# 150306_AriloRX_REV2_0_0.net
KiCad netlist of a schematic drawn in EAGLE
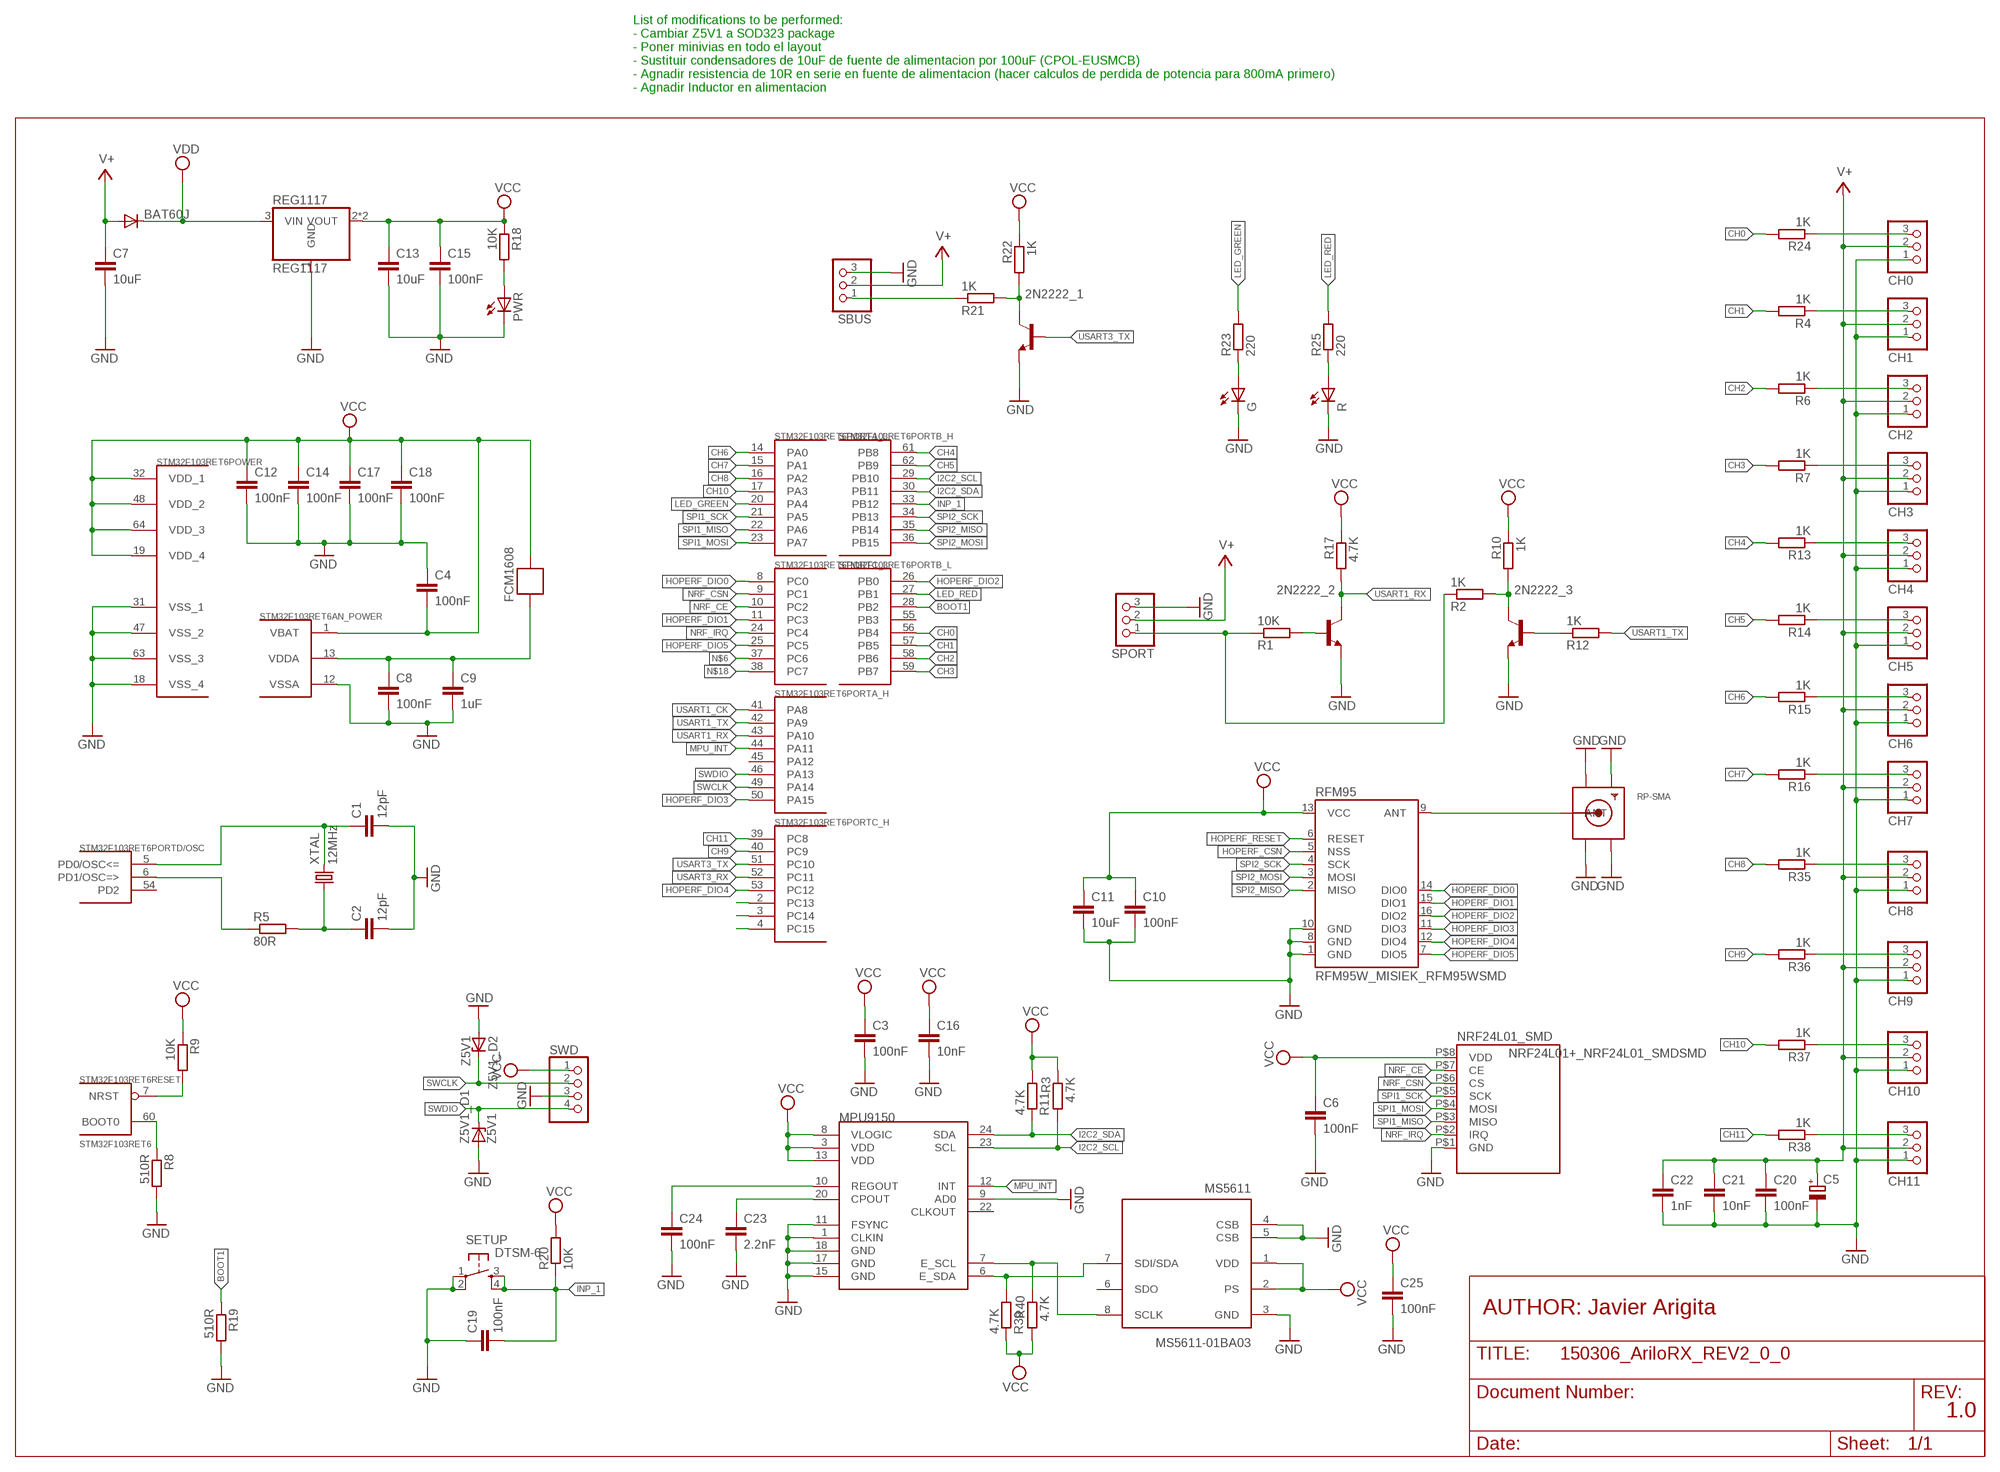
[diagram p0: schematic, sheet 1]

(export (version "E")
  (design (tool "Eeschema 10.0.6"))
  (components
    (comp (ref "2N2222_1")
      (value "MMBT2222ALT1-NPN-SOT23-BEC")
      (footprint "eagle-import:SOT23-BEC")
      (libsource (lib "eagle-import") (part "-NPN-SOT23-BECMMBT2222ALT1"))
    )
    (comp (ref "2N2222_2")
      (value "MMBT2222ALT1-NPN-SOT23-BEC")
      (footprint "eagle-import:SOT23-BEC")
      (libsource (lib "eagle-import") (part "-NPN-SOT23-BECMMBT2222ALT1"))
    )
    (comp (ref "2N2222_3")
      (value "MMBT2222ALT1-NPN-SOT23-BEC")
      (footprint "eagle-import:SOT23-BEC")
      (libsource (lib "eagle-import") (part "-NPN-SOT23-BECMMBT2222ALT1"))
    )
    (comp (ref "BAT60J")
      (value "DIODE-SOD323-R")
      (footprint "eagle-import:SOD323-R")
      (libsource (lib "eagle-import") (part "DIODE-SOD323-R"))
    )
    (comp (ref "C1")
      (value "12pF")
      (footprint "eagle-import:RESISTOR_C0603")
      (libsource (lib "eagle-import") (part "RESISTOR_C-EUC0603"))
    )
    (comp (ref "C2")
      (value "12pF")
      (footprint "eagle-import:RESISTOR_C0603")
      (libsource (lib "eagle-import") (part "RESISTOR_C-EUC0603"))
    )
    (comp (ref "C3")
      (value "100nF")
      (footprint "eagle-import:RESISTOR_C0603")
      (libsource (lib "eagle-import") (part "RESISTOR_C-EUC0603"))
    )
    (comp (ref "C4")
      (value "100nF")
      (footprint "eagle-import:RESISTOR_C0603")
      (libsource (lib "eagle-import") (part "RESISTOR_C-EUC0603"))
    )
    (comp (ref "C5")
      (value "CPOL-EUSMCB")
      (footprint "eagle-import:SMC_B")
      (libsource (lib "eagle-import") (part "CPOL-EUSMCB"))
    )
    (comp (ref "C6")
      (value "100nF")
      (footprint "eagle-import:RESISTOR_C0603")
      (libsource (lib "eagle-import") (part "RESISTOR_C-EUC0603"))
    )
    (comp (ref "C7")
      (value "10uF")
      (footprint "eagle-import:RESISTOR_C3216")
      (libsource (lib "eagle-import") (part "RESISTOR_C-EUC3216"))
    )
    (comp (ref "C8")
      (value "100nF")
      (footprint "eagle-import:RESISTOR_C0603")
      (libsource (lib "eagle-import") (part "RESISTOR_C-EUC0603"))
    )
    (comp (ref "C9")
      (value "1uF")
      (footprint "eagle-import:RESISTOR_C0603")
      (libsource (lib "eagle-import") (part "RESISTOR_C-EUC0603"))
    )
    (comp (ref "C10")
      (value "100nF")
      (footprint "eagle-import:RESISTOR_C0603")
      (libsource (lib "eagle-import") (part "RESISTOR_C-EUC0603"))
    )
    (comp (ref "C11")
      (value "10uF")
      (footprint "eagle-import:RESISTOR_C3216")
      (libsource (lib "eagle-import") (part "RESISTOR_C-EUC3216"))
    )
    (comp (ref "C12")
      (value "100nF")
      (footprint "eagle-import:RESISTOR_C0603")
      (libsource (lib "eagle-import") (part "RESISTOR_C-EUC0603"))
    )
    (comp (ref "C13")
      (value "10uF")
      (footprint "eagle-import:RESISTOR_C3216")
      (libsource (lib "eagle-import") (part "RESISTOR_C-EUC3216"))
    )
    (comp (ref "C14")
      (value "100nF")
      (footprint "eagle-import:RESISTOR_C0603")
      (libsource (lib "eagle-import") (part "RESISTOR_C-EUC0603"))
    )
    (comp (ref "C15")
      (value "100nF")
      (footprint "eagle-import:RESISTOR_C0603")
      (libsource (lib "eagle-import") (part "RESISTOR_C-EUC0603"))
    )
    (comp (ref "C16")
      (value "10nF")
      (footprint "eagle-import:RESISTOR_C0603")
      (libsource (lib "eagle-import") (part "RESISTOR_C-EUC0603"))
    )
    (comp (ref "C17")
      (value "100nF")
      (footprint "eagle-import:RESISTOR_C0603")
      (libsource (lib "eagle-import") (part "RESISTOR_C-EUC0603"))
    )
    (comp (ref "C18")
      (value "100nF")
      (footprint "eagle-import:RESISTOR_C0603")
      (libsource (lib "eagle-import") (part "RESISTOR_C-EUC0603"))
    )
    (comp (ref "C19")
      (value "100nF")
      (footprint "eagle-import:RESISTOR_C0603")
      (libsource (lib "eagle-import") (part "RESISTOR_C-EUC0603"))
    )
    (comp (ref "C20")
      (value "100nF")
      (footprint "eagle-import:RESISTOR_C0603")
      (libsource (lib "eagle-import") (part "RESISTOR_C-EUC0603"))
    )
    (comp (ref "C21")
      (value "10nF")
      (footprint "eagle-import:RESISTOR_C0603")
      (libsource (lib "eagle-import") (part "RESISTOR_C-EUC0603"))
    )
    (comp (ref "C22")
      (value "1nF")
      (footprint "eagle-import:RESISTOR_C0603")
      (libsource (lib "eagle-import") (part "RESISTOR_C-EUC0603"))
    )
    (comp (ref "C23")
      (value "2.2nF")
      (footprint "eagle-import:RESISTOR_C0603")
      (libsource (lib "eagle-import") (part "RESISTOR_C-EUC0603"))
    )
    (comp (ref "C24")
      (value "100nF")
      (footprint "eagle-import:RESISTOR_C0603")
      (libsource (lib "eagle-import") (part "RESISTOR_C-EUC0603"))
    )
    (comp (ref "C25")
      (value "100nF")
      (footprint "eagle-import:RESISTOR_C0603")
      (libsource (lib "eagle-import") (part "RESISTOR_C-EUC0603"))
    )
    (comp (ref "CH0")
      (value "PINHD-1X3")
      (footprint "eagle-import:1X03")
      (libsource (lib "eagle-import") (part "PINHD-1X3"))
    )
    (comp (ref "CH1")
      (value "PINHD-1X3")
      (footprint "eagle-import:1X03")
      (libsource (lib "eagle-import") (part "PINHD-1X3"))
    )
    (comp (ref "CH2")
      (value "PINHD-1X3")
      (footprint "eagle-import:1X03")
      (libsource (lib "eagle-import") (part "PINHD-1X3"))
    )
    (comp (ref "CH3")
      (value "PINHD-1X3")
      (footprint "eagle-import:1X03")
      (libsource (lib "eagle-import") (part "PINHD-1X3"))
    )
    (comp (ref "CH4")
      (value "PINHD-1X3")
      (footprint "eagle-import:1X03")
      (libsource (lib "eagle-import") (part "PINHD-1X3"))
    )
    (comp (ref "CH5")
      (value "PINHD-1X3")
      (footprint "eagle-import:1X03")
      (libsource (lib "eagle-import") (part "PINHD-1X3"))
    )
    (comp (ref "CH6")
      (value "PINHD-1X3")
      (footprint "eagle-import:1X03")
      (libsource (lib "eagle-import") (part "PINHD-1X3"))
    )
    (comp (ref "CH7")
      (value "PINHD-1X3")
      (footprint "eagle-import:1X03")
      (libsource (lib "eagle-import") (part "PINHD-1X3"))
    )
    (comp (ref "CH8")
      (value "PINHD-1X3")
      (footprint "eagle-import:1X03")
      (libsource (lib "eagle-import") (part "PINHD-1X3"))
    )
    (comp (ref "CH9")
      (value "PINHD-1X3")
      (footprint "eagle-import:1X03")
      (libsource (lib "eagle-import") (part "PINHD-1X3"))
    )
    (comp (ref "CH10")
      (value "PINHD-1X3")
      (footprint "eagle-import:1X03")
      (libsource (lib "eagle-import") (part "PINHD-1X3"))
    )
    (comp (ref "CH11")
      (value "PINHD-1X3")
      (footprint "eagle-import:1X03")
      (libsource (lib "eagle-import") (part "PINHD-1X3"))
    )
    (comp (ref "FCM1608")
      (value "FERRITE-BEAD")
      (footprint "eagle-import:R0603")
      (libsource (lib "eagle-import") (part "FERRITE-BEAD"))
    )
    (comp (ref "G")
      (value "LEDCHIP-LED0603")
      (footprint "eagle-import:CHIP-LED0603")
      (libsource (lib "eagle-import") (part "LEDCHIP-LED0603"))
    )
    (comp (ref "MPU9150")
      (value "MPU-9150QFN-24-NP")
      (footprint "eagle-import:QFN-24-NP")
      (libsource (lib "eagle-import") (part "MPU-9150QFN-24-NP"))
    )
    (comp (ref "MS5611")
      (value "MS5611-01BA03")
      (footprint "eagle-import:SON125P300X500X100-8N")
      (libsource (lib "eagle-import") (part "MS5611-01BA03"))
    )
    (comp (ref "NRF24L01_SMD")
      (value "NRF24L01+_NRF24L01_SMDSMD")
      (footprint "eagle-import:NRF24L01+_NRF24L01_SMD")
      (libsource (lib "eagle-import") (part "NRF24L01+_NRF24L01_SMDSMD"))
    )
    (comp (ref "PWR")
      (value "LED_LEDCHIP-LED0603")
      (footprint "eagle-import:LED_CHIP-LED0603")
      (libsource (lib "eagle-import") (part "LED_LEDCHIP-LED0603"))
    )
    (comp (ref "R")
      (value "LEDCHIP-LED0603")
      (footprint "eagle-import:CHIP-LED0603")
      (libsource (lib "eagle-import") (part "LEDCHIP-LED0603"))
    )
    (comp (ref "R1")
      (value "10K")
      (footprint "eagle-import:RCL_R0603")
      (libsource (lib "eagle-import") (part "RCL_R-EU_R0603"))
    )
    (comp (ref "R2")
      (value "1K")
      (footprint "eagle-import:RCL_R0603")
      (libsource (lib "eagle-import") (part "RCL_R-EU_R0603"))
    )
    (comp (ref "R3")
      (value "4.7K")
      (footprint "eagle-import:RCL_R0603")
      (libsource (lib "eagle-import") (part "RCL_R-EU_R0603"))
    )
    (comp (ref "R4")
      (value "1K")
      (footprint "eagle-import:RCL_R0603")
      (libsource (lib "eagle-import") (part "RCL_R-EU_R0603"))
    )
    (comp (ref "R5")
      (value "80R")
      (footprint "eagle-import:RCL_R0603")
      (libsource (lib "eagle-import") (part "RCL_R-EU_R0603"))
    )
    (comp (ref "R6")
      (value "1K")
      (footprint "eagle-import:RCL_R0603")
      (libsource (lib "eagle-import") (part "RCL_R-EU_R0603"))
    )
    (comp (ref "R7")
      (value "1K")
      (footprint "eagle-import:RCL_R0603")
      (libsource (lib "eagle-import") (part "RCL_R-EU_R0603"))
    )
    (comp (ref "R8")
      (value "510R")
      (footprint "eagle-import:RCL_R0603")
      (libsource (lib "eagle-import") (part "RCL_R-EU_R0603"))
    )
    (comp (ref "R9")
      (value "10K")
      (footprint "eagle-import:RCL_R0603")
      (libsource (lib "eagle-import") (part "RCL_R-EU_R0603"))
    )
    (comp (ref "R10")
      (value "1K")
      (footprint "eagle-import:RCL_R0603")
      (libsource (lib "eagle-import") (part "RCL_R-EU_R0603"))
    )
    (comp (ref "R11")
      (value "4.7K")
      (footprint "eagle-import:RCL_R0603")
      (libsource (lib "eagle-import") (part "RCL_R-EU_R0603"))
    )
    (comp (ref "R12")
      (value "1K")
      (footprint "eagle-import:RCL_R0603")
      (libsource (lib "eagle-import") (part "RCL_R-EU_R0603"))
    )
    (comp (ref "R13")
      (value "1K")
      (footprint "eagle-import:RCL_R0603")
      (libsource (lib "eagle-import") (part "RCL_R-EU_R0603"))
    )
    (comp (ref "R14")
      (value "1K")
      (footprint "eagle-import:RCL_R0603")
      (libsource (lib "eagle-import") (part "RCL_R-EU_R0603"))
    )
    (comp (ref "R15")
      (value "1K")
      (footprint "eagle-import:RCL_R0603")
      (libsource (lib "eagle-import") (part "RCL_R-EU_R0603"))
    )
    (comp (ref "R16")
      (value "1K")
      (footprint "eagle-import:RCL_R0603")
      (libsource (lib "eagle-import") (part "RCL_R-EU_R0603"))
    )
    (comp (ref "R17")
      (value "4.7K")
      (footprint "eagle-import:RCL_R0603")
      (libsource (lib "eagle-import") (part "RCL_R-EU_R0603"))
    )
    (comp (ref "R18")
      (value "10K")
      (footprint "eagle-import:RCL_R0603")
      (libsource (lib "eagle-import") (part "RCL_R-EU_R0603"))
    )
    (comp (ref "R19")
      (value "510R")
      (footprint "eagle-import:RCL_R0603")
      (libsource (lib "eagle-import") (part "RCL_R-EU_R0603"))
    )
    (comp (ref "R20")
      (value "10K")
      (footprint "eagle-import:RCL_R0603")
      (libsource (lib "eagle-import") (part "RCL_R-EU_R0603"))
    )
    (comp (ref "R21")
      (value "1K")
      (footprint "eagle-import:RCL_R0603")
      (libsource (lib "eagle-import") (part "RCL_R-EU_R0603"))
    )
    (comp (ref "R22")
      (value "1K")
      (footprint "eagle-import:RCL_R0603")
      (libsource (lib "eagle-import") (part "RCL_R-EU_R0603"))
    )
    (comp (ref "R23")
      (value "220")
      (footprint "eagle-import:RCL_R0603")
      (libsource (lib "eagle-import") (part "RCL_R-EU_R0603"))
    )
    (comp (ref "R24")
      (value "1K")
      (footprint "eagle-import:RCL_R0603")
      (libsource (lib "eagle-import") (part "RCL_R-EU_R0603"))
    )
    (comp (ref "R25")
      (value "220")
      (footprint "eagle-import:RCL_R0603")
      (libsource (lib "eagle-import") (part "RCL_R-EU_R0603"))
    )
    (comp (ref "R35")
      (value "1K")
      (footprint "eagle-import:RCL_R0603")
      (libsource (lib "eagle-import") (part "RCL_R-EU_R0603"))
    )
    (comp (ref "R36")
      (value "1K")
      (footprint "eagle-import:RCL_R0603")
      (libsource (lib "eagle-import") (part "RCL_R-EU_R0603"))
    )
    (comp (ref "R37")
      (value "1K")
      (footprint "eagle-import:RCL_R0603")
      (libsource (lib "eagle-import") (part "RCL_R-EU_R0603"))
    )
    (comp (ref "R38")
      (value "1K")
      (footprint "eagle-import:RCL_R0603")
      (libsource (lib "eagle-import") (part "RCL_R-EU_R0603"))
    )
    (comp (ref "R39")
      (value "4.7K")
      (footprint "eagle-import:RCL_R0603")
      (libsource (lib "eagle-import") (part "RCL_R-EU_R0603"))
    )
    (comp (ref "R40")
      (value "4.7K")
      (footprint "eagle-import:RCL_R0603")
      (libsource (lib "eagle-import") (part "RCL_R-EU_R0603"))
    )
    (comp (ref "REG1117")
      (value "REG1117")
      (footprint "eagle-import:SOT223")
      (libsource (lib "eagle-import") (part "REG1117"))
    )
    (comp (ref "RFM95")
      (value "RFM95W_MISIEK_RFM95WSMD")
      (footprint "eagle-import:RFM95W_MISIEK_RFM95W_SMD")
      (libsource (lib "eagle-import") (part "RFM95W_MISIEK_RFM95WSMD"))
    )
    (comp (ref "RP-SMA")
      (value "SMACONNECTOR_EDGE")
      (footprint "eagle-import:SMA_EDGELAUNCH")
      (libsource (lib "eagle-import") (part "SMACONNECTOR_EDGE"))
    )
    (comp (ref "SBUS")
      (value "PINHD-1X3")
      (footprint "eagle-import:1X03")
      (libsource (lib "eagle-import") (part "PINHD-1X3"))
    )
    (comp (ref "SETUP")
      (value "DTSM-6")
      (footprint "eagle-import:DTSM-6")
      (libsource (lib "eagle-import") (part "DTSM-6"))
    )
    (comp (ref "SPORT")
      (value "PINHD-1X3")
      (footprint "eagle-import:1X03")
      (libsource (lib "eagle-import") (part "PINHD-1X3"))
    )
    (comp (ref "STM32F103RET6")
      (value "STM32F103RET6")
      (footprint "eagle-import:TQFP64")
      (libsource (lib "eagle-import") (part "STM32F10XRXT6"))
    )
    (comp (ref "SWD")
      (value "PINHD-1X4")
      (footprint "eagle-import:1X04")
      (libsource (lib "eagle-import") (part "PINHD-1X4"))
    )
    (comp (ref "XTAL")
      (value "12MHz")
      (footprint "eagle-import:CRYSTAL-SMD-5X3")
      (libsource (lib "eagle-import") (part "CRYSTAL5X3"))
    )
    (comp (ref "Z5V1_D1")
      (value "Z5V1")
      (footprint "eagle-import:SOD80C")
      (libsource (lib "eagle-import") (part "ZENER-DIODESOD80C"))
    )
    (comp (ref "Z5V1_D2")
      (value "Z5V1")
      (footprint "eagle-import:SOD80C")
      (libsource (lib "eagle-import") (part "ZENER-DIODESOD80C"))
    )
  )
  (nets
    (net (code "1") (name "BOOT1") (class "Default")
      (node (ref "R19") (pin "1") (pinfunction "1_1") (pintype "passive"))
      (node (ref "STM32F103RET6") (pin "28") (pinfunction "PB2_28") (pintype "bidirectional"))
    )
    (net (code "2") (name "CH0") (class "Default")
      (node (ref "R24") (pin "2") (pinfunction "2_2") (pintype "passive"))
      (node (ref "STM32F103RET6") (pin "56") (pinfunction "PB4_56") (pintype "bidirectional"))
    )
    (net (code "3") (name "CH1") (class "Default")
      (node (ref "R4") (pin "2") (pinfunction "2_2") (pintype "passive"))
      (node (ref "STM32F103RET6") (pin "57") (pinfunction "PB5_57") (pintype "bidirectional"))
    )
    (net (code "4") (name "CH2") (class "Default")
      (node (ref "R6") (pin "2") (pinfunction "2_2") (pintype "passive"))
      (node (ref "STM32F103RET6") (pin "58") (pinfunction "PB6_58") (pintype "bidirectional"))
    )
    (net (code "5") (name "CH3") (class "Default")
      (node (ref "R7") (pin "2") (pinfunction "2_2") (pintype "passive"))
      (node (ref "STM32F103RET6") (pin "59") (pinfunction "PB7_59") (pintype "bidirectional"))
    )
    (net (code "6") (name "CH4") (class "Default")
      (node (ref "R13") (pin "2") (pinfunction "2_2") (pintype "passive"))
      (node (ref "STM32F103RET6") (pin "61") (pinfunction "PB8_61") (pintype "bidirectional"))
    )
    (net (code "7") (name "CH5") (class "Default")
      (node (ref "R14") (pin "2") (pinfunction "2_2") (pintype "passive"))
      (node (ref "STM32F103RET6") (pin "62") (pinfunction "PB9_62") (pintype "bidirectional"))
    )
    (net (code "8") (name "CH6") (class "Default")
      (node (ref "R15") (pin "2") (pinfunction "2_2") (pintype "passive"))
      (node (ref "STM32F103RET6") (pin "14") (pinfunction "PA0_14") (pintype "bidirectional"))
    )
    (net (code "9") (name "CH7") (class "Default")
      (node (ref "R16") (pin "2") (pinfunction "2_2") (pintype "passive"))
      (node (ref "STM32F103RET6") (pin "15") (pinfunction "PA1_15") (pintype "bidirectional"))
    )
    (net (code "10") (name "CH8") (class "Default")
      (node (ref "R35") (pin "2") (pinfunction "2_2") (pintype "passive"))
      (node (ref "STM32F103RET6") (pin "16") (pinfunction "PA2_16") (pintype "bidirectional"))
    )
    (net (code "11") (name "CH9") (class "Default")
      (node (ref "R36") (pin "2") (pinfunction "2_2") (pintype "passive"))
      (node (ref "STM32F103RET6") (pin "40") (pinfunction "PC9_40") (pintype "bidirectional"))
    )
    (net (code "12") (name "CH10") (class "Default")
      (node (ref "R37") (pin "2") (pinfunction "2_2") (pintype "passive"))
      (node (ref "STM32F103RET6") (pin "17") (pinfunction "PA3_17") (pintype "bidirectional"))
    )
    (net (code "13") (name "CH11") (class "Default")
      (node (ref "R38") (pin "2") (pinfunction "2_2") (pintype "passive"))
      (node (ref "STM32F103RET6") (pin "39") (pinfunction "PC8_39") (pintype "bidirectional"))
    )
    (net (code "14") (name "GND") (class "Default")
      (node (ref "2N2222_1") (pin "E") (pinfunction "E_E") (pintype "passive"))
      (node (ref "2N2222_2") (pin "E") (pinfunction "E_E") (pintype "passive"))
      (node (ref "2N2222_3") (pin "E") (pinfunction "E_E") (pintype "passive"))
      (node (ref "C1") (pin "2") (pinfunction "2_2") (pintype "passive"))
      (node (ref "C10") (pin "2") (pinfunction "2_2") (pintype "passive"))
      (node (ref "C11") (pin "2") (pinfunction "2_2") (pintype "passive"))
      (node (ref "C12") (pin "2") (pinfunction "2_2") (pintype "passive"))
      (node (ref "C13") (pin "2") (pinfunction "2_2") (pintype "passive"))
      (node (ref "C14") (pin "2") (pinfunction "2_2") (pintype "passive"))
      (node (ref "C15") (pin "2") (pinfunction "2_2") (pintype "passive"))
      (node (ref "C16") (pin "2") (pinfunction "2_2") (pintype "passive"))
      (node (ref "C17") (pin "2") (pinfunction "2_2") (pintype "passive"))
      (node (ref "C18") (pin "2") (pinfunction "2_2") (pintype "passive"))
      (node (ref "C19") (pin "1") (pinfunction "1_1") (pintype "passive"))
      (node (ref "C2") (pin "2") (pinfunction "2_2") (pintype "passive"))
      (node (ref "C20") (pin "2") (pinfunction "2_2") (pintype "passive"))
      (node (ref "C21") (pin "2") (pinfunction "2_2") (pintype "passive"))
      (node (ref "C22") (pin "2") (pinfunction "2_2") (pintype "passive"))
      (node (ref "C23") (pin "2") (pinfunction "2_2") (pintype "passive"))
      (node (ref "C24") (pin "2") (pinfunction "2_2") (pintype "passive"))
      (node (ref "C25") (pin "2") (pinfunction "2_2") (pintype "passive"))
      (node (ref "C3") (pin "2") (pinfunction "2_2") (pintype "passive"))
      (node (ref "C4") (pin "1") (pinfunction "1_1") (pintype "passive"))
      (node (ref "C5") (pin "-") (pinfunction "-_-") (pintype "passive"))
      (node (ref "C6") (pin "2") (pinfunction "2_2") (pintype "passive"))
      (node (ref "C7") (pin "2") (pinfunction "2_2") (pintype "passive"))
      (node (ref "C8") (pin "2") (pinfunction "2_2") (pintype "passive"))
      (node (ref "C9") (pin "2") (pinfunction "2_2") (pintype "passive"))
      (node (ref "CH0") (pin "1") (pinfunction "1_1") (pintype "passive"))
      (node (ref "CH1") (pin "1") (pinfunction "1_1") (pintype "passive"))
      (node (ref "CH10") (pin "1") (pinfunction "1_1") (pintype "passive"))
      (node (ref "CH11") (pin "1") (pinfunction "1_1") (pintype "passive"))
      (node (ref "CH2") (pin "1") (pinfunction "1_1") (pintype "passive"))
      (node (ref "CH3") (pin "1") (pinfunction "1_1") (pintype "passive"))
      (node (ref "CH4") (pin "1") (pinfunction "1_1") (pintype "passive"))
      (node (ref "CH5") (pin "1") (pinfunction "1_1") (pintype "passive"))
      (node (ref "CH6") (pin "1") (pinfunction "1_1") (pintype "passive"))
      (node (ref "CH7") (pin "1") (pinfunction "1_1") (pintype "passive"))
      (node (ref "CH8") (pin "1") (pinfunction "1_1") (pintype "passive"))
      (node (ref "CH9") (pin "1") (pinfunction "1_1") (pintype "passive"))
      (node (ref "G") (pin "C") (pinfunction "C_C") (pintype "passive"))
      (node (ref "MPU9150") (pin "1") (pinfunction "CLKIN_1") (pintype "bidirectional"))
      (node (ref "MPU9150") (pin "11") (pinfunction "FSYNC_11") (pintype "bidirectional"))
      (node (ref "MPU9150") (pin "15") (pinfunction "GND_15") (pintype "bidirectional"))
      (node (ref "MPU9150") (pin "17") (pinfunction "GND_17") (pintype "bidirectional"))
      (node (ref "MPU9150") (pin "18") (pinfunction "GND_18") (pintype "bidirectional"))
      (node (ref "MPU9150") (pin "9") (pinfunction "AD0_9") (pintype "bidirectional"))
      (node (ref "MS5611") (pin "3") (pinfunction "GND_3") (pintype "power_in"))
      (node (ref "MS5611") (pin "4") (pinfunction "CSB_4") (pintype "input"))
      (node (ref "MS5611") (pin "5") (pinfunction "CSB_5") (pintype "input"))
      (node (ref "NRF24L01_SMD") (pin "P$1") (pinfunction "GND_P$1") (pintype "power_in"))
      (node (ref "PWR") (pin "C") (pinfunction "C_C") (pintype "passive"))
      (node (ref "R") (pin "C") (pinfunction "C_C") (pintype "passive"))
      (node (ref "R19") (pin "2") (pinfunction "2_2") (pintype "passive"))
      (node (ref "R8") (pin "2") (pinfunction "2_2") (pintype "passive"))
      (node (ref "REG1117") (pin "1") (pinfunction "GND_1") (pintype "power_in"))
      (node (ref "RFM95") (pin "1") (pinfunction "GND_1") (pintype "power_in"))
      (node (ref "RFM95") (pin "10") (pinfunction "GND_10") (pintype "power_in"))
      (node (ref "RFM95") (pin "8") (pinfunction "GND_8") (pintype "power_in"))
      (node (ref "RP-SMA") (pin "GND@1") (pinfunction "GND4_GND@1") (pintype "power_in"))
      (node (ref "RP-SMA") (pin "GND@2") (pinfunction "GND3_GND@2") (pintype "power_in"))
      (node (ref "RP-SMA") (pin "GND@3") (pinfunction "GND2_GND@3") (pintype "power_in"))
      (node (ref "RP-SMA") (pin "GND@4") (pinfunction "GND1_GND@4") (pintype "power_in"))
      (node (ref "SBUS") (pin "3") (pinfunction "3_3") (pintype "passive"))
      (node (ref "SETUP") (pin "1") (pinfunction "1_1") (pintype "passive"))
      (node (ref "SETUP") (pin "2") (pinfunction "2_2") (pintype "passive"))
      (node (ref "SPORT") (pin "3") (pinfunction "3_3") (pintype "passive"))
      (node (ref "STM32F103RET6") (pin "12") (pinfunction "VSSA_12") (pintype "power_in"))
      (node (ref "STM32F103RET6") (pin "18") (pinfunction "VSS_4_18") (pintype "power_in"))
      (node (ref "STM32F103RET6") (pin "31") (pinfunction "VSS_1_31") (pintype "power_in"))
      (node (ref "STM32F103RET6") (pin "47") (pinfunction "VSS_2_47") (pintype "power_in"))
      (node (ref "STM32F103RET6") (pin "63") (pinfunction "VSS_3_63") (pintype "power_in"))
      (node (ref "SWD") (pin "3") (pinfunction "3_3") (pintype "passive"))
      (node (ref "Z5V1_D1") (pin "A") (pinfunction "A_A") (pintype "passive"))
      (node (ref "Z5V1_D2") (pin "A") (pinfunction "A_A") (pintype "passive"))
    )
    (net (code "15") (name "HOPERF_CSN") (class "Default")
      (node (ref "RFM95") (pin "5") (pinfunction "NSS_5") (pintype "input"))
    )
    (net (code "16") (name "HOPERF_DIO0") (class "Default")
      (node (ref "RFM95") (pin "14") (pinfunction "DIO0_14") (pintype "input"))
      (node (ref "STM32F103RET6") (pin "8") (pinfunction "PC0_8") (pintype "bidirectional"))
    )
    (net (code "17") (name "HOPERF_DIO1") (class "Default")
      (node (ref "RFM95") (pin "15") (pinfunction "DIO1_15") (pintype "input"))
      (node (ref "STM32F103RET6") (pin "11") (pinfunction "PC3_11") (pintype "bidirectional"))
    )
    (net (code "18") (name "HOPERF_DIO2") (class "Default")
      (node (ref "RFM95") (pin "16") (pinfunction "DIO2_16") (pintype "input"))
      (node (ref "STM32F103RET6") (pin "26") (pinfunction "PB0_26") (pintype "bidirectional"))
    )
    (net (code "19") (name "HOPERF_DIO3") (class "Default")
      (node (ref "RFM95") (pin "11") (pinfunction "DIO3_11") (pintype "bidirectional"))
      (node (ref "STM32F103RET6") (pin "50") (pinfunction "PA15_50") (pintype "bidirectional"))
    )
    (net (code "20") (name "HOPERF_DIO4") (class "Default")
      (node (ref "RFM95") (pin "12") (pinfunction "DIO4_12") (pintype "bidirectional"))
      (node (ref "STM32F103RET6") (pin "53") (pinfunction "PC12_53") (pintype "bidirectional"))
    )
    (net (code "21") (name "HOPERF_DIO5") (class "Default")
      (node (ref "RFM95") (pin "7") (pinfunction "DIO5_7") (pintype "bidirectional"))
      (node (ref "STM32F103RET6") (pin "25") (pinfunction "PC5_25") (pintype "bidirectional"))
    )
    (net (code "22") (name "HOPERF_RESET") (class "Default")
      (node (ref "RFM95") (pin "6") (pinfunction "RESET_6") (pintype "output"))
    )
    (net (code "23") (name "I2C2_SCL") (class "Default")
      (node (ref "MPU9150") (pin "23") (pinfunction "SCL_23") (pintype "bidirectional"))
      (node (ref "R3") (pin "2") (pinfunction "2_2") (pintype "passive"))
      (node (ref "STM32F103RET6") (pin "29") (pinfunction "PB10_29") (pintype "bidirectional"))
    )
    (net (code "24") (name "I2C2_SDA") (class "Default")
      (node (ref "MPU9150") (pin "24") (pinfunction "SDA_24") (pintype "bidirectional"))
      (node (ref "R11") (pin "1") (pinfunction "1_1") (pintype "passive"))
      (node (ref "STM32F103RET6") (pin "30") (pinfunction "PB11_30") (pintype "bidirectional"))
    )
    (net (code "25") (name "INP_1") (class "Default")
      (node (ref "C19") (pin "2") (pinfunction "2_2") (pintype "passive"))
      (node (ref "R20") (pin "1") (pinfunction "1_1") (pintype "passive"))
      (node (ref "SETUP") (pin "3") (pinfunction "3_3") (pintype "passive"))
      (node (ref "SETUP") (pin "4") (pinfunction "4_4") (pintype "passive"))
      (node (ref "STM32F103RET6") (pin "33") (pinfunction "PB12_33") (pintype "bidirectional"))
    )
    (net (code "26") (name "LED_GREEN") (class "Default")
      (node (ref "R23") (pin "2") (pinfunction "2_2") (pintype "passive"))
      (node (ref "STM32F103RET6") (pin "20") (pinfunction "PA4_20") (pintype "bidirectional"))
    )
    (net (code "27") (name "LED_RED") (class "Default")
      (node (ref "R25") (pin "2") (pinfunction "2_2") (pintype "passive"))
      (node (ref "STM32F103RET6") (pin "27") (pinfunction "PB1_27") (pintype "bidirectional"))
    )
    (net (code "28") (name "MPU_INT") (class "Default")
      (node (ref "MPU9150") (pin "12") (pinfunction "INT_12") (pintype "bidirectional"))
      (node (ref "STM32F103RET6") (pin "44") (pinfunction "PA11_44") (pintype "bidirectional"))
    )
    (net (code "29") (name "N$6") (class "Default")
      (node (ref "STM32F103RET6") (pin "37") (pinfunction "PC6_37") (pintype "bidirectional"))
    )
    (net (code "30") (name "N$18") (class "Default")
      (node (ref "STM32F103RET6") (pin "38") (pinfunction "PC7_38") (pintype "bidirectional"))
    )
    (net (code "31") (name "NRF_CE") (class "Default")
      (node (ref "NRF24L01_SMD") (pin "P$7") (pinfunction "CE_P$7") (pintype "input"))
      (node (ref "STM32F103RET6") (pin "10") (pinfunction "PC2_10") (pintype "bidirectional"))
    )
    (net (code "32") (name "NRF_CSN") (class "Default")
      (node (ref "NRF24L01_SMD") (pin "P$6") (pinfunction "CS_P$6") (pintype "input"))
      (node (ref "STM32F103RET6") (pin "9") (pinfunction "PC1_9") (pintype "bidirectional"))
    )
    (net (code "33") (name "NRF_IRQ") (class "Default")
      (node (ref "NRF24L01_SMD") (pin "P$2") (pinfunction "IRQ_P$2") (pintype "output"))
      (node (ref "STM32F103RET6") (pin "24") (pinfunction "PC4_24") (pintype "bidirectional"))
    )
    (net (code "34") (name "Net-(2N2222_1-PadC)") (class "Default")
      (node (ref "2N2222_1") (pin "C") (pinfunction "C_C") (pintype "passive"))
      (node (ref "R21") (pin "2") (pinfunction "2_2") (pintype "passive"))
      (node (ref "R22") (pin "2") (pinfunction "2_2") (pintype "passive"))
    )
    (net (code "35") (name "Net-(2N2222_2-PadB)") (class "Default")
      (node (ref "2N2222_2") (pin "B") (pinfunction "B_B") (pintype "passive"))
      (node (ref "R1") (pin "2") (pinfunction "2_2") (pintype "passive"))
    )
    (net (code "36") (name "Net-(2N2222_3-PadB)") (class "Default")
      (node (ref "2N2222_3") (pin "B") (pinfunction "B_B") (pintype "passive"))
      (node (ref "R12") (pin "1") (pinfunction "1_1") (pintype "passive"))
    )
    (net (code "37") (name "Net-(2N2222_3-PadC)") (class "Default")
      (node (ref "2N2222_3") (pin "C") (pinfunction "C_C") (pintype "passive"))
      (node (ref "R10") (pin "2") (pinfunction "2_2") (pintype "passive"))
      (node (ref "R2") (pin "2") (pinfunction "2_2") (pintype "passive"))
    )
    (net (code "38") (name "Net-(C2-Pad1)") (class "Default")
      (node (ref "C2") (pin "1") (pinfunction "1_1") (pintype "passive"))
      (node (ref "R5") (pin "2") (pinfunction "2_2") (pintype "passive"))
      (node (ref "XTAL") (pin "1") (pinfunction "1_1") (pintype "passive"))
    )
    (net (code "39") (name "Net-(CH0-Pad3)") (class "Default")
      (node (ref "CH0") (pin "3") (pinfunction "3_3") (pintype "passive"))
      (node (ref "R24") (pin "1") (pinfunction "1_1") (pintype "passive"))
    )
    (net (code "40") (name "Net-(CH1-Pad3)") (class "Default")
      (node (ref "CH1") (pin "3") (pinfunction "3_3") (pintype "passive"))
      (node (ref "R4") (pin "1") (pinfunction "1_1") (pintype "passive"))
    )
    (net (code "41") (name "Net-(CH2-Pad3)") (class "Default")
      (node (ref "CH2") (pin "3") (pinfunction "3_3") (pintype "passive"))
      (node (ref "R6") (pin "1") (pinfunction "1_1") (pintype "passive"))
    )
    (net (code "42") (name "Net-(CH3-Pad3)") (class "Default")
      (node (ref "CH3") (pin "3") (pinfunction "3_3") (pintype "passive"))
      (node (ref "R7") (pin "1") (pinfunction "1_1") (pintype "passive"))
    )
    (net (code "43") (name "Net-(CH4-Pad3)") (class "Default")
      (node (ref "CH4") (pin "3") (pinfunction "3_3") (pintype "passive"))
      (node (ref "R13") (pin "1") (pinfunction "1_1") (pintype "passive"))
    )
    (net (code "44") (name "Net-(CH5-Pad3)") (class "Default")
      (node (ref "CH5") (pin "3") (pinfunction "3_3") (pintype "passive"))
      (node (ref "R14") (pin "1") (pinfunction "1_1") (pintype "passive"))
    )
    (net (code "45") (name "Net-(CH6-Pad3)") (class "Default")
      (node (ref "CH6") (pin "3") (pinfunction "3_3") (pintype "passive"))
      (node (ref "R15") (pin "1") (pinfunction "1_1") (pintype "passive"))
    )
    (net (code "46") (name "Net-(CH7-Pad3)") (class "Default")
      (node (ref "CH7") (pin "3") (pinfunction "3_3") (pintype "passive"))
      (node (ref "R16") (pin "1") (pinfunction "1_1") (pintype "passive"))
    )
    (net (code "47") (name "Net-(CH8-Pad3)") (class "Default")
      (node (ref "CH8") (pin "3") (pinfunction "3_3") (pintype "passive"))
      (node (ref "R35") (pin "1") (pinfunction "1_1") (pintype "passive"))
    )
    (net (code "48") (name "Net-(CH9-Pad3)") (class "Default")
      (node (ref "CH9") (pin "3") (pinfunction "3_3") (pintype "passive"))
      (node (ref "R36") (pin "1") (pinfunction "1_1") (pintype "passive"))
    )
    (net (code "49") (name "Net-(CH10-Pad3)") (class "Default")
      (node (ref "CH10") (pin "3") (pinfunction "3_3") (pintype "passive"))
      (node (ref "R37") (pin "1") (pinfunction "1_1") (pintype "passive"))
    )
    (net (code "50") (name "Net-(CH11-Pad3)") (class "Default")
      (node (ref "CH11") (pin "3") (pinfunction "3_3") (pintype "passive"))
      (node (ref "R38") (pin "1") (pinfunction "1_1") (pintype "passive"))
    )
    (net (code "51") (name "Net-(FCM1608-P$2)") (class "Default")
      (node (ref "C8") (pin "1") (pinfunction "1_1") (pintype "passive"))
      (node (ref "C9") (pin "1") (pinfunction "1_1") (pintype "passive"))
      (node (ref "FCM1608") (pin "2") (pinfunction "P$2_2") (pintype "bidirectional"))
      (node (ref "STM32F103RET6") (pin "13") (pinfunction "VDDA_13") (pintype "power_in"))
    )
    (net (code "52") (name "Net-(G-PadA)") (class "Default")
      (node (ref "G") (pin "A") (pinfunction "A_A") (pintype "passive"))
      (node (ref "R23") (pin "1") (pinfunction "1_1") (pintype "passive"))
    )
    (net (code "53") (name "Net-(MPU9150-CPOUT)") (class "Default")
      (node (ref "C23") (pin "1") (pinfunction "1_1") (pintype "passive"))
      (node (ref "MPU9150") (pin "20") (pinfunction "CPOUT_20") (pintype "bidirectional"))
    )
    (net (code "54") (name "Net-(MPU9150-E_SCL)") (class "Default")
      (node (ref "MPU9150") (pin "7") (pinfunction "E_SCL_7") (pintype "bidirectional"))
      (node (ref "MS5611") (pin "8") (pinfunction "SCLK_8") (pintype "input"))
      (node (ref "R40") (pin "1") (pinfunction "1_1") (pintype "passive"))
    )
    (net (code "55") (name "Net-(MPU9150-E_SDA)") (class "Default")
      (node (ref "MPU9150") (pin "6") (pinfunction "E_SDA_6") (pintype "bidirectional"))
      (node (ref "MS5611") (pin "7") (pinfunction "SDI/SDA_7") (pintype "bidirectional"))
      (node (ref "R39") (pin "2") (pinfunction "2_2") (pintype "passive"))
    )
    (net (code "56") (name "Net-(MPU9150-REGOUT)") (class "Default")
      (node (ref "C24") (pin "1") (pinfunction "1_1") (pintype "passive"))
      (node (ref "MPU9150") (pin "10") (pinfunction "REGOUT_10") (pintype "bidirectional"))
    )
    (net (code "57") (name "Net-(PWR-PadA)") (class "Default")
      (node (ref "PWR") (pin "A") (pinfunction "A_A") (pintype "passive"))
      (node (ref "R18") (pin "2") (pinfunction "2_2") (pintype "passive"))
    )
    (net (code "58") (name "Net-(R-PadA)") (class "Default")
      (node (ref "R") (pin "A") (pinfunction "A_A") (pintype "passive"))
      (node (ref "R25") (pin "1") (pinfunction "1_1") (pintype "passive"))
    )
    (net (code "59") (name "Net-(R1-Pad1)") (class "Default")
      (node (ref "R1") (pin "1") (pinfunction "1_1") (pintype "passive"))
      (node (ref "R2") (pin "1") (pinfunction "1_1") (pintype "passive"))
      (node (ref "SPORT") (pin "1") (pinfunction "1_1") (pintype "passive"))
    )
    (net (code "60") (name "Net-(R21-Pad1)") (class "Default")
      (node (ref "R21") (pin "1") (pinfunction "1_1") (pintype "passive"))
      (node (ref "SBUS") (pin "1") (pinfunction "1_1") (pintype "passive"))
    )
    (net (code "61") (name "Net-(RFM95-ANT)") (class "Default")
      (node (ref "RFM95") (pin "9") (pinfunction "ANT_9") (pintype "bidirectional"))
      (node (ref "RP-SMA") (pin "P") (pinfunction "ANT_P") (pintype "bidirectional"))
    )
    (net (code "62") (name "Net-(STM32F103RET6H-PD0{slash}OSC<=)") (class "Default")
      (node (ref "C1") (pin "1") (pinfunction "1_1") (pintype "passive"))
      (node (ref "STM32F103RET6") (pin "5") (pinfunction "PD0/OSC<=_5") (pintype "bidirectional"))
      (node (ref "XTAL") (pin "3") (pinfunction "2_3") (pintype "passive"))
    )
    (net (code "63") (name "Net-(STM32F103RET6H-PD1{slash}OSC=>)") (class "Default")
      (node (ref "R5") (pin "1") (pinfunction "1_1") (pintype "passive"))
      (node (ref "STM32F103RET6") (pin "6") (pinfunction "PD1/OSC=>_6") (pintype "bidirectional"))
    )
    (net (code "64") (name "Net-(STM32F103RET6J-BOOT0)") (class "Default")
      (node (ref "R8") (pin "1") (pinfunction "1_1") (pintype "passive"))
      (node (ref "STM32F103RET6") (pin "60") (pinfunction "BOOT0_60") (pintype "input"))
    )
    (net (code "65") (name "Net-(STM32F103RET6J-NRST)") (class "Default")
      (node (ref "R9") (pin "2") (pinfunction "2_2") (pintype "passive"))
      (node (ref "STM32F103RET6") (pin "7") (pinfunction "NRST_7") (pintype "input"))
    )
    (net (code "66") (name "SPI1_MISO") (class "Default")
      (node (ref "NRF24L01_SMD") (pin "P$3") (pinfunction "MISO_P$3") (pintype "output"))
      (node (ref "STM32F103RET6") (pin "22") (pinfunction "PA6_22") (pintype "bidirectional"))
    )
    (net (code "67") (name "SPI1_MOSI") (class "Default")
      (node (ref "NRF24L01_SMD") (pin "P$4") (pinfunction "MOSI_P$4") (pintype "input"))
      (node (ref "STM32F103RET6") (pin "23") (pinfunction "PA7_23") (pintype "bidirectional"))
    )
    (net (code "68") (name "SPI1_SCK") (class "Default")
      (node (ref "NRF24L01_SMD") (pin "P$5") (pinfunction "SCK_P$5") (pintype "input"))
      (node (ref "STM32F103RET6") (pin "21") (pinfunction "PA5_21") (pintype "bidirectional"))
    )
    (net (code "69") (name "SPI2_MISO") (class "Default")
      (node (ref "RFM95") (pin "2") (pinfunction "MISO_2") (pintype "output"))
      (node (ref "STM32F103RET6") (pin "35") (pinfunction "PB14_35") (pintype "bidirectional"))
    )
    (net (code "70") (name "SPI2_MOSI") (class "Default")
      (node (ref "RFM95") (pin "3") (pinfunction "MOSI_3") (pintype "input"))
      (node (ref "STM32F103RET6") (pin "36") (pinfunction "PB15_36") (pintype "bidirectional"))
    )
    (net (code "71") (name "SPI2_SCK") (class "Default")
      (node (ref "RFM95") (pin "4") (pinfunction "SCK_4") (pintype "input"))
      (node (ref "STM32F103RET6") (pin "34") (pinfunction "PB13_34") (pintype "bidirectional"))
    )
    (net (code "72") (name "SWCLK") (class "Default")
      (node (ref "STM32F103RET6") (pin "49") (pinfunction "PA14_49") (pintype "bidirectional"))
      (node (ref "SWD") (pin "2") (pinfunction "2_2") (pintype "passive"))
      (node (ref "Z5V1_D2") (pin "C") (pinfunction "C_C") (pintype "passive"))
    )
    (net (code "73") (name "SWDIO") (class "Default")
      (node (ref "STM32F103RET6") (pin "46") (pinfunction "PA13_46") (pintype "bidirectional"))
      (node (ref "SWD") (pin "4") (pinfunction "4_4") (pintype "passive"))
      (node (ref "Z5V1_D1") (pin "C") (pinfunction "C_C") (pintype "passive"))
    )
    (net (code "74") (name "USART1_CK") (class "Default")
      (node (ref "STM32F103RET6") (pin "41") (pinfunction "PA8_41") (pintype "bidirectional"))
    )
    (net (code "75") (name "USART1_RX") (class "Default")
      (node (ref "2N2222_2") (pin "C") (pinfunction "C_C") (pintype "passive"))
      (node (ref "R17") (pin "2") (pinfunction "2_2") (pintype "passive"))
      (node (ref "STM32F103RET6") (pin "43") (pinfunction "PA10_43") (pintype "bidirectional"))
    )
    (net (code "76") (name "USART1_TX") (class "Default")
      (node (ref "R12") (pin "2") (pinfunction "2_2") (pintype "passive"))
      (node (ref "STM32F103RET6") (pin "42") (pinfunction "PA9_42") (pintype "bidirectional"))
    )
    (net (code "77") (name "USART3_RX") (class "Default")
      (node (ref "STM32F103RET6") (pin "52") (pinfunction "PC11_52") (pintype "bidirectional"))
    )
    (net (code "78") (name "USART3_TX") (class "Default")
      (node (ref "2N2222_1") (pin "B") (pinfunction "B_B") (pintype "passive"))
      (node (ref "STM32F103RET6") (pin "51") (pinfunction "PC10_51") (pintype "bidirectional"))
    )
    (net (code "79") (name "V+") (class "Default")
      (node (ref "BAT60J") (pin "A") (pinfunction "A_A") (pintype "passive"))
      (node (ref "C20") (pin "1") (pinfunction "1_1") (pintype "passive"))
      (node (ref "C21") (pin "1") (pinfunction "1_1") (pintype "passive"))
      (node (ref "C22") (pin "1") (pinfunction "1_1") (pintype "passive"))
      (node (ref "C5") (pin "+") (pinfunction "+_+") (pintype "passive"))
      (node (ref "C7") (pin "1") (pinfunction "1_1") (pintype "passive"))
      (node (ref "CH0") (pin "2") (pinfunction "2_2") (pintype "passive"))
      (node (ref "CH1") (pin "2") (pinfunction "2_2") (pintype "passive"))
      (node (ref "CH10") (pin "2") (pinfunction "2_2") (pintype "passive"))
      (node (ref "CH11") (pin "2") (pinfunction "2_2") (pintype "passive"))
      (node (ref "CH2") (pin "2") (pinfunction "2_2") (pintype "passive"))
      (node (ref "CH3") (pin "2") (pinfunction "2_2") (pintype "passive"))
      (node (ref "CH4") (pin "2") (pinfunction "2_2") (pintype "passive"))
      (node (ref "CH5") (pin "2") (pinfunction "2_2") (pintype "passive"))
      (node (ref "CH6") (pin "2") (pinfunction "2_2") (pintype "passive"))
      (node (ref "CH7") (pin "2") (pinfunction "2_2") (pintype "passive"))
      (node (ref "CH8") (pin "2") (pinfunction "2_2") (pintype "passive"))
      (node (ref "CH9") (pin "2") (pinfunction "2_2") (pintype "passive"))
      (node (ref "SBUS") (pin "2") (pinfunction "2_2") (pintype "passive"))
      (node (ref "SPORT") (pin "2") (pinfunction "2_2") (pintype "passive"))
    )
    (net (code "80") (name "VCC") (class "Default")
      (node (ref "C10") (pin "1") (pinfunction "1_1") (pintype "passive"))
      (node (ref "C11") (pin "1") (pinfunction "1_1") (pintype "passive"))
      (node (ref "C12") (pin "1") (pinfunction "1_1") (pintype "passive"))
      (node (ref "C13") (pin "1") (pinfunction "1_1") (pintype "passive"))
      (node (ref "C14") (pin "1") (pinfunction "1_1") (pintype "passive"))
      (node (ref "C15") (pin "1") (pinfunction "1_1") (pintype "passive"))
      (node (ref "C16") (pin "1") (pinfunction "1_1") (pintype "passive"))
      (node (ref "C17") (pin "1") (pinfunction "1_1") (pintype "passive"))
      (node (ref "C18") (pin "1") (pinfunction "1_1") (pintype "passive"))
      (node (ref "C25") (pin "1") (pinfunction "1_1") (pintype "passive"))
      (node (ref "C3") (pin "1") (pinfunction "1_1") (pintype "passive"))
      (node (ref "C4") (pin "2") (pinfunction "2_2") (pintype "passive"))
      (node (ref "C6") (pin "1") (pinfunction "1_1") (pintype "passive"))
      (node (ref "FCM1608") (pin "1") (pinfunction "P$1_1") (pintype "bidirectional"))
      (node (ref "MPU9150") (pin "13") (pinfunction "VDD_13") (pintype "bidirectional"))
      (node (ref "MPU9150") (pin "3") (pinfunction "VDD_3") (pintype "bidirectional"))
      (node (ref "MPU9150") (pin "8") (pinfunction "VLOGIC_8") (pintype "bidirectional"))
      (node (ref "MS5611") (pin "1") (pinfunction "VDD_1") (pintype "power_in"))
      (node (ref "MS5611") (pin "2") (pinfunction "PS_2") (pintype "input"))
      (node (ref "NRF24L01_SMD") (pin "P$8") (pinfunction "VDD_P$8") (pintype "bidirectional"))
      (node (ref "R10") (pin "1") (pinfunction "1_1") (pintype "passive"))
      (node (ref "R11") (pin "2") (pinfunction "2_2") (pintype "passive"))
      (node (ref "R17") (pin "1") (pinfunction "1_1") (pintype "passive"))
      (node (ref "R18") (pin "1") (pinfunction "1_1") (pintype "passive"))
      (node (ref "R20") (pin "2") (pinfunction "2_2") (pintype "passive"))
      (node (ref "R22") (pin "1") (pinfunction "1_1") (pintype "passive"))
      (node (ref "R3") (pin "1") (pinfunction "1_1") (pintype "passive"))
      (node (ref "R39") (pin "1") (pinfunction "1_1") (pintype "passive"))
      (node (ref "R40") (pin "2") (pinfunction "2_2") (pintype "passive"))
      (node (ref "R9") (pin "1") (pinfunction "1_1") (pintype "passive"))
      (node (ref "REG1117") (pin "2") (pinfunction "VOUT_2") (pintype "power_in"))
      (node (ref "REG1117") (pin "4") (pinfunction "VOUT_4") (pintype "power_in"))
      (node (ref "RFM95") (pin "13") (pinfunction "VCC_13") (pintype "bidirectional"))
      (node (ref "STM32F103RET6") (pin "1") (pinfunction "VBAT_1") (pintype "power_in"))
      (node (ref "STM32F103RET6") (pin "19") (pinfunction "VDD_4_19") (pintype "power_in"))
      (node (ref "STM32F103RET6") (pin "32") (pinfunction "VDD_1_32") (pintype "power_in"))
      (node (ref "STM32F103RET6") (pin "48") (pinfunction "VDD_2_48") (pintype "power_in"))
      (node (ref "STM32F103RET6") (pin "64") (pinfunction "VDD_3_64") (pintype "power_in"))
      (node (ref "SWD") (pin "1") (pinfunction "1_1") (pintype "passive"))
    )
    (net (code "81") (name "VDD") (class "Default")
      (node (ref "BAT60J") (pin "C") (pinfunction "C_C") (pintype "passive"))
      (node (ref "REG1117") (pin "3") (pinfunction "VIN_3") (pintype "input"))
    )
    (net (code "82") (name "unconnected-(MPU9150-CLKOUT-Pad22)") (class "Default")
      (node (ref "MPU9150") (pin "22") (pinfunction "CLKOUT_22") (pintype "bidirectional"))
    )
    (net (code "83") (name "unconnected-(MS5611-SDO-Pad6)") (class "Default")
      (node (ref "MS5611") (pin "6") (pinfunction "SDO_6") (pintype "output"))
    )
    (net (code "84") (name "unconnected-(STM32F103RET6B-PA12-Pad45)") (class "Default")
      (node (ref "STM32F103RET6") (pin "45") (pinfunction "PA12_45") (pintype "bidirectional"))
    )
    (net (code "85") (name "unconnected-(STM32F103RET6E-PB3-Pad55)") (class "Default")
      (node (ref "STM32F103RET6") (pin "55") (pinfunction "PB3_55") (pintype "bidirectional"))
    )
    (net (code "86") (name "unconnected-(STM32F103RET6F-PC13-Pad2)") (class "Default")
      (node (ref "STM32F103RET6") (pin "2") (pinfunction "PC13_2") (pintype "bidirectional"))
    )
    (net (code "87") (name "unconnected-(STM32F103RET6F-PC14-Pad3)") (class "Default")
      (node (ref "STM32F103RET6") (pin "3") (pinfunction "PC14_3") (pintype "bidirectional"))
    )
    (net (code "88") (name "unconnected-(STM32F103RET6F-PC15-Pad4)") (class "Default")
      (node (ref "STM32F103RET6") (pin "4") (pinfunction "PC15_4") (pintype "bidirectional"))
    )
    (net (code "89") (name "unconnected-(STM32F103RET6H-PD2-Pad54)") (class "Default")
      (node (ref "STM32F103RET6") (pin "54") (pinfunction "PD2_54") (pintype "bidirectional"))
    )
  )
)
